# uSD_CARD_molex.net
KiCad netlist of a schematic drawn in Altium Designer
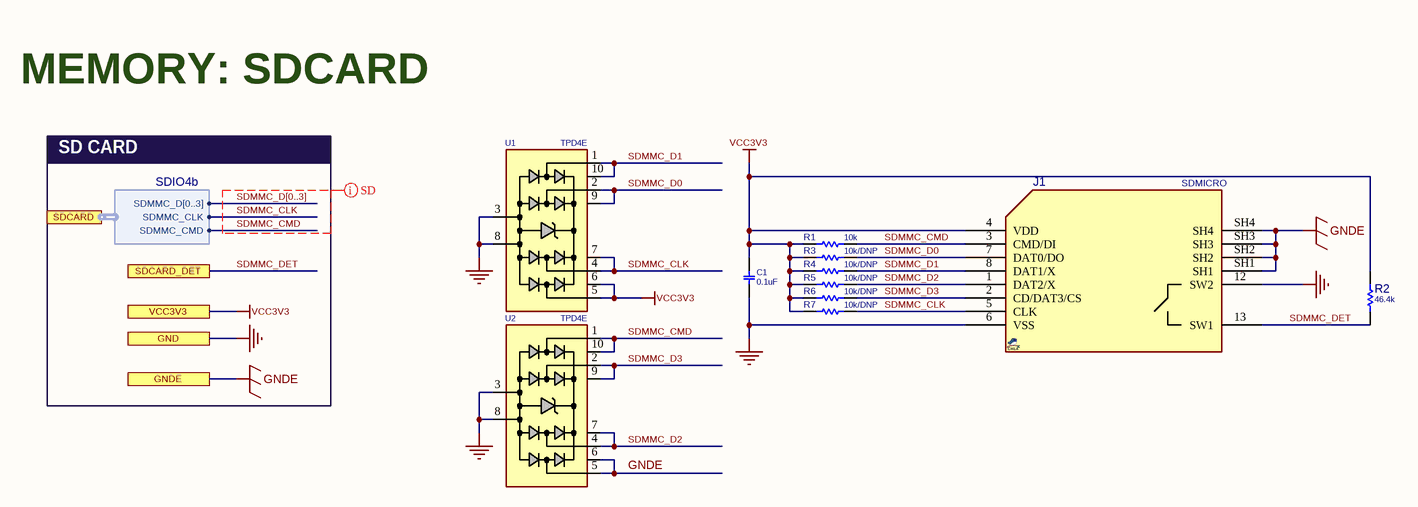
[diagram p0: uSD_CARD_molex.SchDoc]

(export (version "E")
  (design (tool "Eeschema 10.0.6"))
  (components
    (comp (ref "C1")
      (value "0.1uF")
      (footprint "C0402")
      (description "CAP, MLCC")
      (fields (field (name "MANF_P#") "GRM155R61E104") (field (name "MANF") "Murata"))
      (libsource (lib "mlcc_smd_passive") (part "CAP_SMD_MLCC_100n50TDK"))
    )
    (comp (ref "J1")
      (value "SDMICRO")
      (footprint "SDMICRO_MOLEX104031")
      (description "CONN MICRO SD R/A PUSHin-PULLout SMD")
      (fields (field (name "MANF") "Molex") (field (name "MANF_P#") "104031-0811"))
      (libsource (lib "socket_card") (part "SOCKET_SDMICRO_MOLEX104031"))
    )
    (comp (ref "R1")
      (value "10k")
      (footprint "R0402")
      (description "RESISTOR, SMD")
      (libsource (lib "passive_res_smd") (part "RES_SMD"))
    )
    (comp (ref "R2")
      (value "46.4k")
      (footprint "R0402")
      (description "RESISTOR, SMD")
      (libsource (lib "passive_res_smd") (part "RES_SMD"))
    )
    (comp (ref "R3")
      (value "10k/DNP")
      (footprint "R0402")
      (description "RESISTOR, SMD")
      (libsource (lib "passive_res_smd") (part "RES_SMD"))
    )
    (comp (ref "R4")
      (value "10k/DNP")
      (footprint "R0402")
      (description "RESISTOR, SMD")
      (libsource (lib "passive_res_smd") (part "RES_SMD"))
    )
    (comp (ref "R5")
      (value "10k/DNP")
      (footprint "R0402")
      (description "RESISTOR, SMD")
      (libsource (lib "passive_res_smd") (part "RES_SMD"))
    )
    (comp (ref "R6")
      (value "10k/DNP")
      (footprint "R0402")
      (description "RESISTOR, SMD")
      (libsource (lib "passive_res_smd") (part "RES_SMD"))
    )
    (comp (ref "R7")
      (value "10k/DNP")
      (footprint "R0402")
      (description "RESISTOR, SMD")
      (libsource (lib "passive_res_smd") (part "RES_SMD"))
    )
    (comp (ref "U1")
      (value "TPD4E")
      (footprint "SON50_10_2510")
      (description "TVS, ESD PROTECT, 4CH,")
      (fields (field (name "MANF_P#") "TPD4E05U06DQA") (field (name "MANF") "Texas Instruments"))
      (libsource (lib "protect_tvs_esd_fuse") (part "TVS_X4_TPD4E05U06"))
    )
    (comp (ref "U2")
      (value "TPD4E")
      (footprint "SON50_10_2510")
      (description "TVS, ESD PROTECT, 4CH,")
      (fields (field (name "MANF_P#") "TPD4E05U06DQA") (field (name "MANF") "Texas Instruments"))
      (libsource (lib "protect_tvs_esd_fuse") (part "TVS_X4_TPD4E05U06"))
    )
  )
  (nets
    (net (code "2") (name "/SDMMC_CLK") (class "Default")
      (node (ref "J1") (pin "5") (pinfunction "CLK_5") (pintype "passive"))
      (node (ref "R7") (pin "2") (pinfunction "2_2") (pintype "passive"))
      (node (ref "U1") (pin "4") (pinfunction "4_4") (pintype "passive"))
      (node (ref "U1") (pin "7") (pinfunction "7_7") (pintype "passive"))
    )
    (net (code "3") (name "/SDMMC_CMD") (class "Default")
      (node (ref "J1") (pin "3") (pinfunction "CMD/DI_3") (pintype "passive"))
      (node (ref "R1") (pin "2") (pinfunction "2_2") (pintype "passive"))
      (node (ref "U2") (pin "1") (pinfunction "1_1") (pintype "passive"))
      (node (ref "U2") (pin "10") (pinfunction "10_10") (pintype "passive"))
    )
    (net (code "4") (name "/SDMMC_D0") (class "Default")
      (node (ref "J1") (pin "7") (pinfunction "DAT0/DO_7") (pintype "passive"))
      (node (ref "R3") (pin "2") (pinfunction "2_2") (pintype "passive"))
      (node (ref "U1") (pin "2") (pinfunction "2_2") (pintype "passive"))
      (node (ref "U1") (pin "9") (pinfunction "9_9") (pintype "passive"))
    )
    (net (code "5") (name "/SDMMC_D1") (class "Default")
      (node (ref "J1") (pin "8") (pinfunction "DAT1/X_8") (pintype "passive"))
      (node (ref "R4") (pin "2") (pinfunction "2_2") (pintype "passive"))
      (node (ref "U1") (pin "1") (pinfunction "1_1") (pintype "passive"))
      (node (ref "U1") (pin "10") (pinfunction "10_10") (pintype "passive"))
    )
    (net (code "6") (name "/SDMMC_D2") (class "Default")
      (node (ref "J1") (pin "1") (pinfunction "DAT2/X_1") (pintype "passive"))
      (node (ref "R5") (pin "2") (pinfunction "2_2") (pintype "passive"))
      (node (ref "U2") (pin "4") (pinfunction "4_4") (pintype "passive"))
      (node (ref "U2") (pin "7") (pinfunction "7_7") (pintype "passive"))
    )
    (net (code "7") (name "/SDMMC_D3") (class "Default")
      (node (ref "J1") (pin "2") (pinfunction "CD/DAT3/CS_2") (pintype "passive"))
      (node (ref "R6") (pin "2") (pinfunction "2_2") (pintype "passive"))
      (node (ref "U2") (pin "2") (pinfunction "2_2") (pintype "passive"))
      (node (ref "U2") (pin "9") (pinfunction "9_9") (pintype "passive"))
    )
    (net (code "8") (name "/SDMMC_DET") (class "Default")
      (node (ref "J1") (pin "13") (pinfunction "SW1_13") (pintype "passive"))
      (node (ref "R2") (pin "1") (pinfunction "1_1") (pintype "passive"))
    )
    (net (code "11") (name "GND") (class "Default")
      (node (ref "C1") (pin "2") (pinfunction "2_2") (pintype "passive"))
      (node (ref "J1") (pin "12") (pinfunction "SW2_12") (pintype "passive"))
      (node (ref "J1") (pin "6") (pinfunction "VSS_6") (pintype "passive"))
      (node (ref "U1") (pin "3") (pinfunction "3_3") (pintype "passive"))
      (node (ref "U1") (pin "8") (pinfunction "8_8") (pintype "passive"))
      (node (ref "U2") (pin "3") (pinfunction "3_3") (pintype "passive"))
      (node (ref "U2") (pin "8") (pinfunction "8_8") (pintype "passive"))
    )
    (net (code "12") (name "GNDE") (class "Default")
      (node (ref "J1") (pin "SH1") (pinfunction "SH1_SH1") (pintype "passive"))
      (node (ref "J1") (pin "SH2") (pinfunction "SH2_SH2") (pintype "passive"))
      (node (ref "J1") (pin "SH3") (pinfunction "SH3_SH3") (pintype "passive"))
      (node (ref "J1") (pin "SH4") (pinfunction "SH4_SH4") (pintype "passive"))
      (node (ref "U2") (pin "5") (pinfunction "5_5") (pintype "passive"))
      (node (ref "U2") (pin "6") (pinfunction "6_6") (pintype "passive"))
    )
    (net (code "13") (name "VCC3V3") (class "Default")
      (node (ref "C1") (pin "1") (pinfunction "1_1") (pintype "passive"))
      (node (ref "J1") (pin "4") (pinfunction "VDD_4") (pintype "passive"))
      (node (ref "R1") (pin "1") (pinfunction "1_1") (pintype "passive"))
      (node (ref "R2") (pin "2") (pinfunction "2_2") (pintype "passive"))
      (node (ref "R3") (pin "1") (pinfunction "1_1") (pintype "passive"))
      (node (ref "R4") (pin "1") (pinfunction "1_1") (pintype "passive"))
      (node (ref "R5") (pin "1") (pinfunction "1_1") (pintype "passive"))
      (node (ref "R6") (pin "1") (pinfunction "1_1") (pintype "passive"))
      (node (ref "R7") (pin "1") (pinfunction "1_1") (pintype "passive"))
      (node (ref "U1") (pin "5") (pinfunction "5_5") (pintype "passive"))
      (node (ref "U1") (pin "6") (pinfunction "6_6") (pintype "passive"))
    )
  )
)
